# mbedshield037.net
KiCad netlist of a schematic drawn in EAGLE
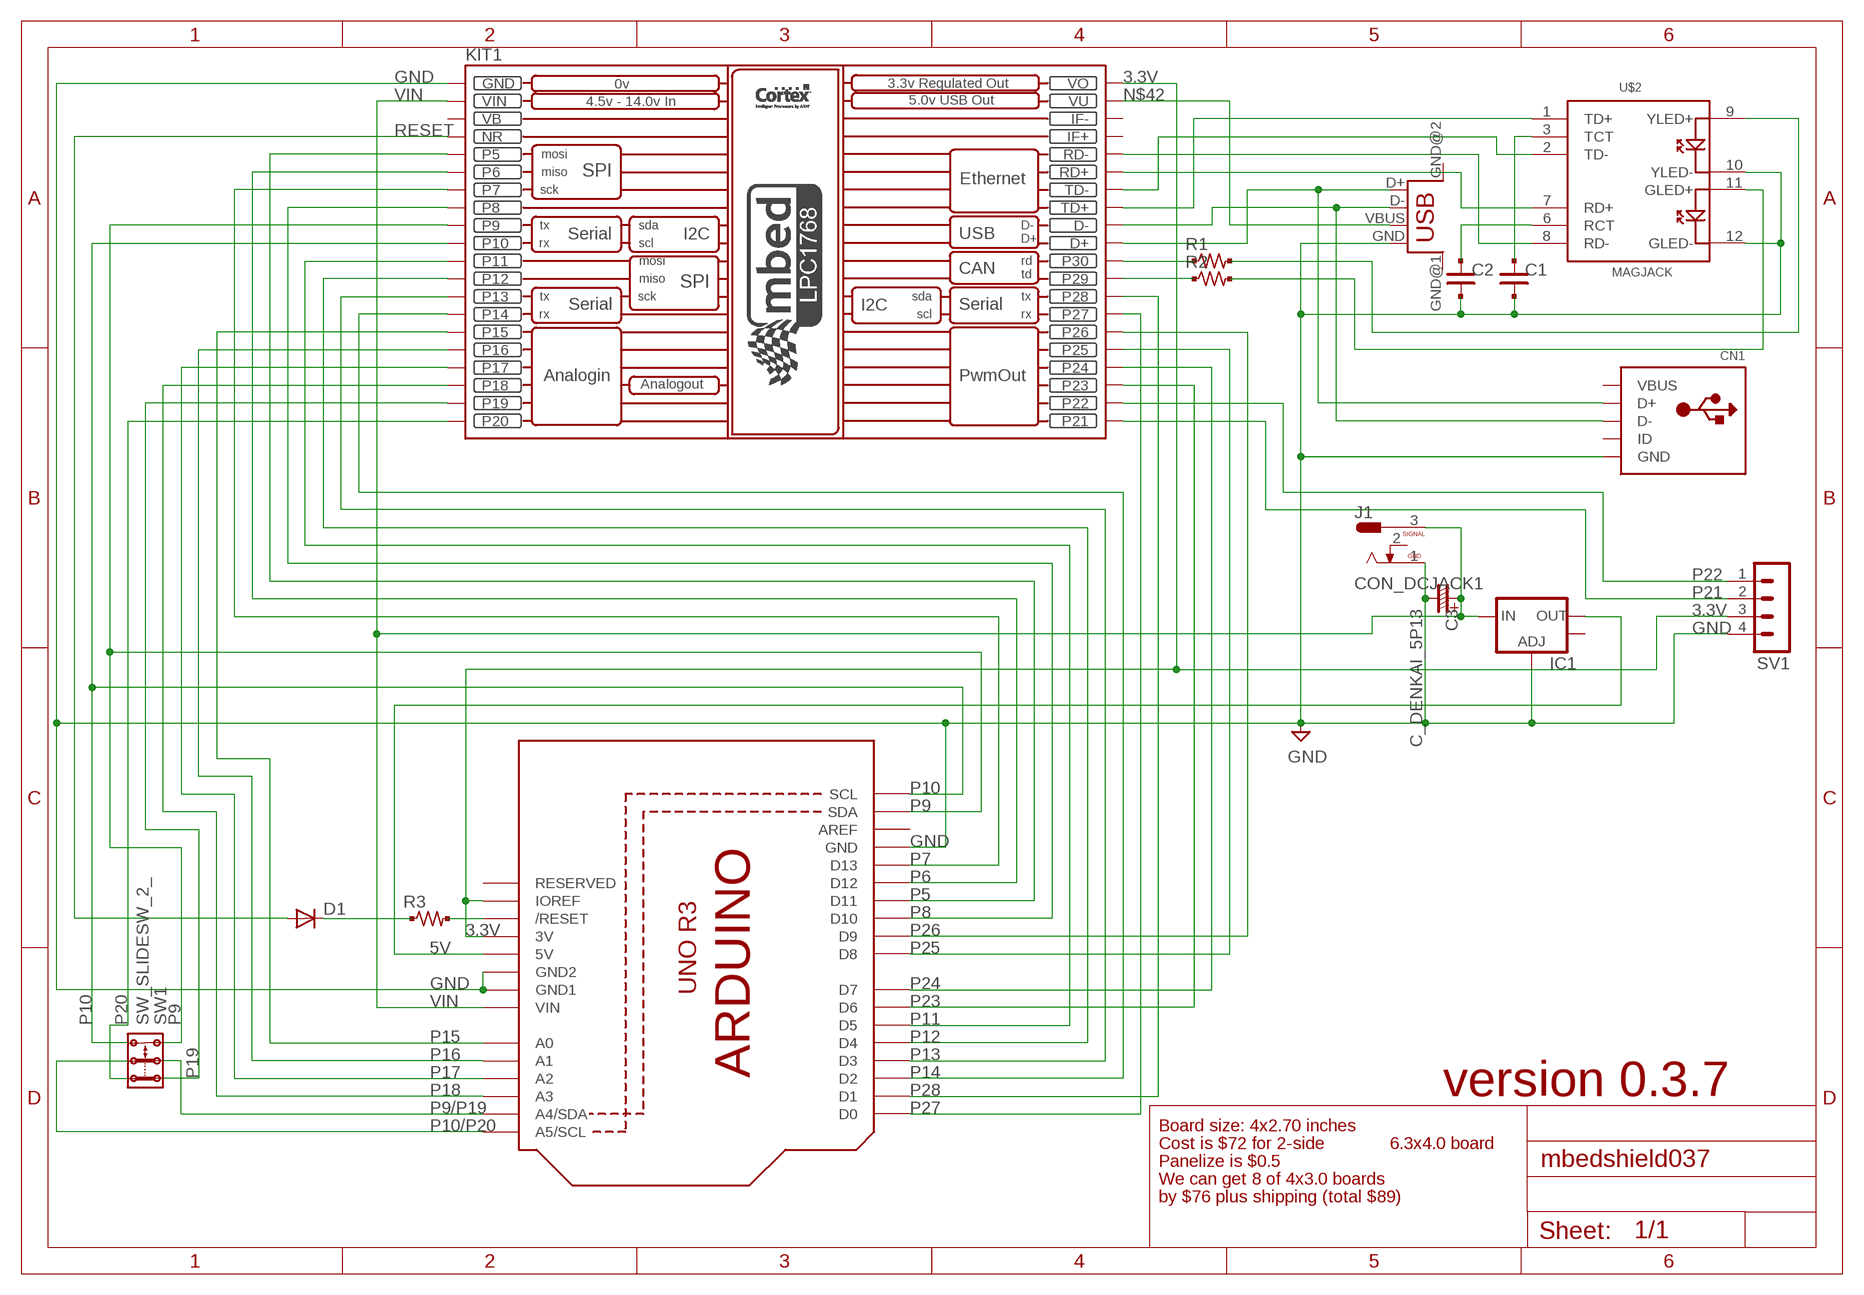
[diagram p0: schematic, sheet 1]

(export (version "E")
  (design (tool "Eeschema 10.0.6"))
  (components
    (comp (ref "C1")
      (value "C_PAD_PAD_2125")
      (footprint "eagle-import:CR_2125")
      (libsource (lib "eagle-import") (part "C_PAD_PAD_2125"))
    )
    (comp (ref "C2")
      (value "C_PAD_PAD_2125")
      (footprint "eagle-import:CR_2125")
      (libsource (lib "eagle-import") (part "C_PAD_PAD_2125"))
    )
    (comp (ref "C3")
      (value "C_DENKAI_5P13")
      (footprint "eagle-import:C_2.5PHI6")
      (libsource (lib "eagle-import") (part "C_DENKAI_2.5P6"))
    )
    (comp (ref "CN1")
      (value "USBMINIB")
      (footprint "eagle-import:USB-MINIB")
      (libsource (lib "eagle-import") (part "USBMINIB"))
    )
    (comp (ref "D1")
      (value "DIODE_SMALL_FLAT_2V")
      (footprint "eagle-import:DIODE_2125_2VIA")
      (libsource (lib "eagle-import") (part "DIODE_SMALL_FLAT_2V"))
    )
    (comp (ref "IC1")
      (value "V_REG_LM1117SOT223")
      (footprint "eagle-import:SOT223")
      (libsource (lib "eagle-import") (part "V_REG_LM1117SOT223"))
    )
    (comp (ref "J1")
      (value "CON_DCJACK1")
      (footprint "eagle-import:CON_DCJACK")
      (libsource (lib "eagle-import") (part "CON_DCJACK1"))
    )
    (comp (ref "KIT1")
      (value "MBED_NXP_LPC1768")
      (footprint "eagle-import:MBED-KIT")
      (libsource (lib "eagle-import") (part "MBED_NXP_LPC1768"))
    )
    (comp (ref "R1")
      (value "R_US_PAD_PAD_1608")
      (footprint "eagle-import:R_1608_PADPAD")
      (libsource (lib "eagle-import") (part "R_US_PAD_PAD_1608"))
    )
    (comp (ref "R2")
      (value "R_US_PAD_PAD_1608")
      (footprint "eagle-import:R_1608_PADPAD")
      (libsource (lib "eagle-import") (part "R_US_PAD_PAD_1608"))
    )
    (comp (ref "R3")
      (value "R_US_PAD_PAD_1608")
      (footprint "eagle-import:R_1608_PADPAD")
      (libsource (lib "eagle-import") (part "R_US_PAD_PAD_1608"))
    )
    (comp (ref "SV1")
      (value "MA04-1")
      (footprint "eagle-import:MA04-1")
      (libsource (lib "eagle-import") (part "MA04-1"))
    )
    (comp (ref "SW1")
      (value "SW_SLIDESW_2_")
      (footprint "eagle-import:SW_SLIDE_2X2_1")
      (libsource (lib "eagle-import") (part "SW_SLIDESW_2_"))
    )
    (comp (ref "U$2")
      (value "MAGJACK")
      (footprint "eagle-import:MAGJACK")
      (libsource (lib "eagle-import") (part "MAGJACK"))
    )
    (comp (ref "U1")
      (value "ARDUINOR3-DIMENSION")
      (footprint "eagle-import:ARDUINOR3")
      (libsource (lib "eagle-import") (part "ARDUINOR3-DIMENSION"))
    )
    (comp (ref "USB")
      (value "USB")
      (footprint "eagle-import:USB-FEMALE-A-PTH")
      (libsource (lib "eagle-import") (part "USB"))
    )
  )
  (nets
    (net (code "1") (name "/3.3V") (class "Default")
      (node (ref "KIT1") (pin "VOUT") (pinfunction "VO_VOUT") (pintype "power_in"))
      (node (ref "SV1") (pin "3") (pinfunction "3_3") (pintype "passive"))
      (node (ref "U1") (pin "3V") (pinfunction "3V_3V") (pintype "power_in"))
      (node (ref "U1") (pin "IOREF") (pinfunction "IOREF_IOREF") (pintype "output"))
    )
    (net (code "2") (name "/5V") (class "Default")
      (node (ref "IC1") (pin "2") (pinfunction "OUT_2") (pintype "output"))
      (node (ref "U1") (pin "5V") (pinfunction "5V_5V") (pintype "power_in"))
    )
    (net (code "3") (name "/N$42") (class "Default")
      (node (ref "KIT1") (pin "VU") (pinfunction "VU_VU") (pintype "power_in"))
      (node (ref "USB") (pin "VBUS") (pinfunction "VBUS_VBUS") (pintype "bidirectional"))
    )
    (net (code "4") (name "/P5") (class "Default")
      (node (ref "KIT1") (pin "P$5") (pinfunction "P5_P$5") (pintype "bidirectional"))
      (node (ref "U1") (pin "D11") (pinfunction "D11_D11") (pintype "bidirectional"))
    )
    (net (code "5") (name "/P6") (class "Default")
      (node (ref "KIT1") (pin "P$6") (pinfunction "P6_P$6") (pintype "bidirectional"))
      (node (ref "U1") (pin "D12") (pinfunction "D12_D12") (pintype "bidirectional"))
    )
    (net (code "6") (name "/P7") (class "Default")
      (node (ref "KIT1") (pin "P$7") (pinfunction "P7_P$7") (pintype "bidirectional"))
      (node (ref "U1") (pin "D13") (pinfunction "D13_D13") (pintype "bidirectional"))
    )
    (net (code "7") (name "/P8") (class "Default")
      (node (ref "KIT1") (pin "P$8") (pinfunction "P8_P$8") (pintype "bidirectional"))
      (node (ref "U1") (pin "D10") (pinfunction "D10_D10") (pintype "bidirectional"))
    )
    (net (code "8") (name "/P9") (class "Default")
      (node (ref "KIT1") (pin "P$9") (pinfunction "P9_P$9") (pintype "bidirectional"))
      (node (ref "SW1") (pin "2.1") (pinfunction "2.1_2.1") (pintype "passive"))
      (node (ref "U1") (pin "SDA") (pinfunction "SDA_SDA") (pintype "bidirectional"))
    )
    (net (code "9") (name "/P9{slash}P19") (class "Default")
      (node (ref "SW1") (pin "COM.1") (pinfunction "COM.1_COM.1") (pintype "passive"))
      (node (ref "U1") (pin "A4") (pinfunction "A4/SDA_A4") (pintype "bidirectional"))
    )
    (net (code "10") (name "/P10") (class "Default")
      (node (ref "KIT1") (pin "P$10") (pinfunction "P10_P$10") (pintype "bidirectional"))
      (node (ref "SW1") (pin "2.2") (pinfunction "2.2_2.2") (pintype "passive"))
      (node (ref "U1") (pin "SCL") (pinfunction "SCL_SCL") (pintype "bidirectional"))
    )
    (net (code "11") (name "/P10{slash}P20") (class "Default")
      (node (ref "SW1") (pin "COM.2") (pinfunction "COM.2_COM.2") (pintype "passive"))
      (node (ref "U1") (pin "A5") (pinfunction "A5/SCL_A5") (pintype "bidirectional"))
    )
    (net (code "12") (name "/P11") (class "Default")
      (node (ref "KIT1") (pin "P$11") (pinfunction "P11_P$11") (pintype "bidirectional"))
      (node (ref "U1") (pin "D5") (pinfunction "D5_D5") (pintype "bidirectional"))
    )
    (net (code "13") (name "/P12") (class "Default")
      (node (ref "KIT1") (pin "P$12") (pinfunction "P12_P$12") (pintype "bidirectional"))
      (node (ref "U1") (pin "D4") (pinfunction "D4_D4") (pintype "bidirectional"))
    )
    (net (code "14") (name "/P13") (class "Default")
      (node (ref "KIT1") (pin "P$13") (pinfunction "P13_P$13") (pintype "bidirectional"))
      (node (ref "U1") (pin "D3") (pinfunction "D3_D3") (pintype "bidirectional"))
    )
    (net (code "15") (name "/P14") (class "Default")
      (node (ref "KIT1") (pin "P$14") (pinfunction "P14_P$14") (pintype "bidirectional"))
      (node (ref "U1") (pin "D2") (pinfunction "D2_D2") (pintype "bidirectional"))
    )
    (net (code "16") (name "/P15") (class "Default")
      (node (ref "KIT1") (pin "P$15") (pinfunction "P15_P$15") (pintype "bidirectional"))
      (node (ref "U1") (pin "A0") (pinfunction "A0_A0") (pintype "bidirectional"))
    )
    (net (code "17") (name "/P16") (class "Default")
      (node (ref "KIT1") (pin "P$16") (pinfunction "P16_P$16") (pintype "bidirectional"))
      (node (ref "U1") (pin "A1") (pinfunction "A1_A1") (pintype "bidirectional"))
    )
    (net (code "18") (name "/P17") (class "Default")
      (node (ref "KIT1") (pin "P$17") (pinfunction "P17_P$17") (pintype "bidirectional"))
      (node (ref "U1") (pin "A2") (pinfunction "A2_A2") (pintype "bidirectional"))
    )
    (net (code "19") (name "/P18") (class "Default")
      (node (ref "KIT1") (pin "P$18") (pinfunction "P18_P$18") (pintype "bidirectional"))
      (node (ref "U1") (pin "A3") (pinfunction "A3_A3") (pintype "bidirectional"))
    )
    (net (code "20") (name "/P19") (class "Default")
      (node (ref "KIT1") (pin "P$19") (pinfunction "P19_P$19") (pintype "bidirectional"))
      (node (ref "SW1") (pin "1.1") (pinfunction "1.1_1.1") (pintype "passive"))
    )
    (net (code "21") (name "/P20") (class "Default")
      (node (ref "KIT1") (pin "P$20") (pinfunction "P20_P$20") (pintype "bidirectional"))
      (node (ref "SW1") (pin "1.2") (pinfunction "1.2_1.2") (pintype "passive"))
    )
    (net (code "22") (name "/P21") (class "Default")
      (node (ref "KIT1") (pin "P$21") (pinfunction "P21_P$21") (pintype "bidirectional"))
      (node (ref "SV1") (pin "2") (pinfunction "2_2") (pintype "passive"))
    )
    (net (code "23") (name "/P22") (class "Default")
      (node (ref "KIT1") (pin "P$22") (pinfunction "P22_P$22") (pintype "bidirectional"))
      (node (ref "SV1") (pin "1") (pinfunction "1_1") (pintype "passive"))
    )
    (net (code "24") (name "/P23") (class "Default")
      (node (ref "KIT1") (pin "P$23") (pinfunction "P23_P$23") (pintype "bidirectional"))
      (node (ref "U1") (pin "D6") (pinfunction "D6_D6") (pintype "bidirectional"))
    )
    (net (code "25") (name "/P24") (class "Default")
      (node (ref "KIT1") (pin "P$24") (pinfunction "P24_P$24") (pintype "bidirectional"))
      (node (ref "U1") (pin "D7") (pinfunction "D7_D7") (pintype "bidirectional"))
    )
    (net (code "26") (name "/P25") (class "Default")
      (node (ref "KIT1") (pin "P$25") (pinfunction "P25_P$25") (pintype "bidirectional"))
      (node (ref "U1") (pin "D8") (pinfunction "D8_D8") (pintype "bidirectional"))
    )
    (net (code "27") (name "/P26") (class "Default")
      (node (ref "KIT1") (pin "P$26") (pinfunction "P26_P$26") (pintype "bidirectional"))
      (node (ref "U1") (pin "D9") (pinfunction "D9_D9") (pintype "bidirectional"))
    )
    (net (code "28") (name "/P27") (class "Default")
      (node (ref "KIT1") (pin "P$27") (pinfunction "P27_P$27") (pintype "bidirectional"))
      (node (ref "U1") (pin "D0") (pinfunction "D0_D0") (pintype "bidirectional"))
    )
    (net (code "29") (name "/P28") (class "Default")
      (node (ref "KIT1") (pin "P$28") (pinfunction "P28_P$28") (pintype "bidirectional"))
      (node (ref "U1") (pin "D1") (pinfunction "D1_D1") (pintype "bidirectional"))
    )
    (net (code "30") (name "/RESET") (class "Default")
      (node (ref "D1") (pin "A") (pinfunction "A_A") (pintype "passive"))
      (node (ref "KIT1") (pin "NR") (pinfunction "NR_NR") (pintype "power_in"))
    )
    (net (code "31") (name "/VB") (class "Default")
      (node (ref "KIT1") (pin "VB") (pinfunction "VB_VB") (pintype "power_in"))
    )
    (net (code "32") (name "/VBUS") (class "Default")
      (node (ref "CN1") (pin "VBUS") (pinfunction "VBUS_VBUS") (pintype "power_in"))
    )
    (net (code "33") (name "/VIN") (class "Default")
      (node (ref "C3") (pin "+") (pinfunction "+_+") (pintype "passive"))
      (node (ref "IC1") (pin "3") (pinfunction "IN_3") (pintype "input"))
      (node (ref "J1") (pin "3") (pinfunction "1_3") (pintype "passive"))
      (node (ref "KIT1") (pin "VIN") (pinfunction "VIN_VIN") (pintype "power_in"))
      (node (ref "U1") (pin "VIN") (pinfunction "VIN_VIN") (pintype "power_in"))
    )
    (net (code "34") (name "GND") (class "Default")
      (node (ref "C1") (pin "2") (pinfunction "2_2") (pintype "passive"))
      (node (ref "C2") (pin "2") (pinfunction "2_2") (pintype "passive"))
      (node (ref "C3") (pin "-") (pinfunction "-_-") (pintype "passive"))
      (node (ref "CN1") (pin "GND") (pinfunction "GND_GND") (pintype "power_in"))
      (node (ref "IC1") (pin "1") (pinfunction "ADJ_1") (pintype "input"))
      (node (ref "J1") (pin "1") (pinfunction "3_1") (pintype "passive"))
      (node (ref "KIT1") (pin "GND") (pinfunction "GND_GND") (pintype "power_in"))
      (node (ref "SV1") (pin "4") (pinfunction "4_4") (pintype "passive"))
      (node (ref "U$2") (pin "10") (pinfunction "YLED-_10") (pintype "bidirectional"))
      (node (ref "U$2") (pin "12") (pinfunction "GLED-_12") (pintype "bidirectional"))
      (node (ref "U1") (pin "GND") (pinfunction "GND_GND") (pintype "power_in"))
      (node (ref "U1") (pin "GND1") (pinfunction "GND1_GND1") (pintype "power_in"))
      (node (ref "U1") (pin "GND2") (pinfunction "GND2_GND2") (pintype "power_in"))
      (node (ref "USB") (pin "GND") (pinfunction "GND_GND") (pintype "bidirectional"))
    )
    (net (code "35") (name "Net-(CN1-PadD+)") (class "Default")
      (node (ref "CN1") (pin "D+") (pinfunction "D+_D+") (pintype "bidirectional"))
      (node (ref "KIT1") (pin "D+") (pinfunction "D+_D+") (pintype "bidirectional"))
      (node (ref "USB") (pin "D+") (pinfunction "D+_D+") (pintype "bidirectional"))
    )
    (net (code "36") (name "Net-(CN1-PadD-)") (class "Default")
      (node (ref "CN1") (pin "D-") (pinfunction "D-_D-") (pintype "bidirectional"))
      (node (ref "KIT1") (pin "D-") (pinfunction "D-_D-") (pintype "bidirectional"))
      (node (ref "USB") (pin "D-") (pinfunction "D-_D-") (pintype "bidirectional"))
    )
    (net (code "37") (name "Net-(D1-C)") (class "Default")
      (node (ref "D1") (pin "K") (pinfunction "C_K") (pintype "passive"))
      (node (ref "R3") (pin "1") (pinfunction "1_1") (pintype "passive"))
    )
    (net (code "38") (name "Net-(KIT1-P29)") (class "Default")
      (node (ref "KIT1") (pin "P$29") (pinfunction "P29_P$29") (pintype "bidirectional"))
      (node (ref "R2") (pin "1") (pinfunction "1_1") (pintype "passive"))
    )
    (net (code "39") (name "Net-(KIT1-P30)") (class "Default")
      (node (ref "KIT1") (pin "P$30") (pinfunction "P30_P$30") (pintype "bidirectional"))
      (node (ref "R1") (pin "1") (pinfunction "1_1") (pintype "passive"))
    )
    (net (code "40") (name "Net-(U$2-GLED+)") (class "Default")
      (node (ref "R2") (pin "2") (pinfunction "2_2") (pintype "passive"))
      (node (ref "U$2") (pin "11") (pinfunction "GLED+_11") (pintype "bidirectional"))
    )
    (net (code "41") (name "Net-(U$2-RCT)") (class "Default")
      (node (ref "C2") (pin "1") (pinfunction "1_1") (pintype "passive"))
      (node (ref "U$2") (pin "6") (pinfunction "RCT_6") (pintype "bidirectional"))
    )
    (net (code "42") (name "Net-(U$2-RD+)") (class "Default")
      (node (ref "KIT1") (pin "RD+") (pinfunction "RD+_RD+") (pintype "bidirectional"))
      (node (ref "U$2") (pin "7") (pinfunction "RD+_7") (pintype "bidirectional"))
    )
    (net (code "43") (name "Net-(U$2-RD-)") (class "Default")
      (node (ref "KIT1") (pin "RD-") (pinfunction "RD-_RD-") (pintype "bidirectional"))
      (node (ref "U$2") (pin "8") (pinfunction "RD-_8") (pintype "bidirectional"))
    )
    (net (code "44") (name "Net-(U$2-TCT)") (class "Default")
      (node (ref "C1") (pin "1") (pinfunction "1_1") (pintype "passive"))
      (node (ref "U$2") (pin "3") (pinfunction "TCT_3") (pintype "bidirectional"))
    )
    (net (code "45") (name "Net-(U$2-TD+)") (class "Default")
      (node (ref "KIT1") (pin "TD+") (pinfunction "TD+_TD+") (pintype "bidirectional"))
      (node (ref "U$2") (pin "1") (pinfunction "TD+_1") (pintype "bidirectional"))
    )
    (net (code "46") (name "Net-(U$2-TD-)") (class "Default")
      (node (ref "KIT1") (pin "TD-") (pinfunction "TD-_TD-") (pintype "bidirectional"))
      (node (ref "U$2") (pin "2") (pinfunction "TD-_2") (pintype "bidirectional"))
    )
    (net (code "47") (name "Net-(U$2-YLED+)") (class "Default")
      (node (ref "R1") (pin "2") (pinfunction "2_2") (pintype "passive"))
      (node (ref "U$2") (pin "9") (pinfunction "YLED+_9") (pintype "bidirectional"))
    )
    (net (code "48") (name "Net-(U1-{slash}RESET)") (class "Default")
      (node (ref "R3") (pin "2") (pinfunction "2_2") (pintype "passive"))
      (node (ref "U1") (pin "RESET") (pinfunction "/RESET_RESET") (pintype "bidirectional"))
    )
    (net (code "49") (name "unconnected-(CN1-PadID)") (class "Default")
      (node (ref "CN1") (pin "ID") (pinfunction "ID_ID") (pintype "bidirectional"))
    )
    (net (code "50") (name "unconnected-(IC1-OUT-Pad4)") (class "Default")
      (node (ref "IC1") (pin "4") (pinfunction "OUT_4") (pintype "output"))
    )
    (net (code "51") (name "unconnected-(J1-Pad2)") (class "Default")
      (node (ref "J1") (pin "2") (pinfunction "2_2") (pintype "passive"))
    )
    (net (code "52") (name "unconnected-(KIT1-PadIF+)") (class "Default")
      (node (ref "KIT1") (pin "IF+") (pinfunction "IF+_IF+") (pintype "bidirectional"))
    )
    (net (code "53") (name "unconnected-(KIT1-PadIF-)") (class "Default")
      (node (ref "KIT1") (pin "IF-") (pinfunction "IF-_IF-") (pintype "bidirectional"))
    )
    (net (code "54") (name "unconnected-(U1-PadAREF)") (class "Default")
      (node (ref "U1") (pin "AREF") (pinfunction "AREF_AREF") (pintype "bidirectional"))
    )
    (net (code "55") (name "unconnected-(U1-PadRESERVED)") (class "Default")
      (node (ref "U1") (pin "RESERVED") (pinfunction "RESERVED_RESERVED") (pintype "no_connect"))
    )
    (net (code "56") (name "unconnected-(USB-GND-PadGND@1)") (class "Default")
      (node (ref "USB") (pin "GND@1") (pinfunction "GND_GND@1") (pintype "bidirectional"))
    )
    (net (code "57") (name "unconnected-(USB-GND-PadGND@2)") (class "Default")
      (node (ref "USB") (pin "GND@2") (pinfunction "GND_GND@2") (pintype "bidirectional"))
    )
  )
)
